# Sheet1.net
KiCad netlist of a schematic drawn in Altium Designer
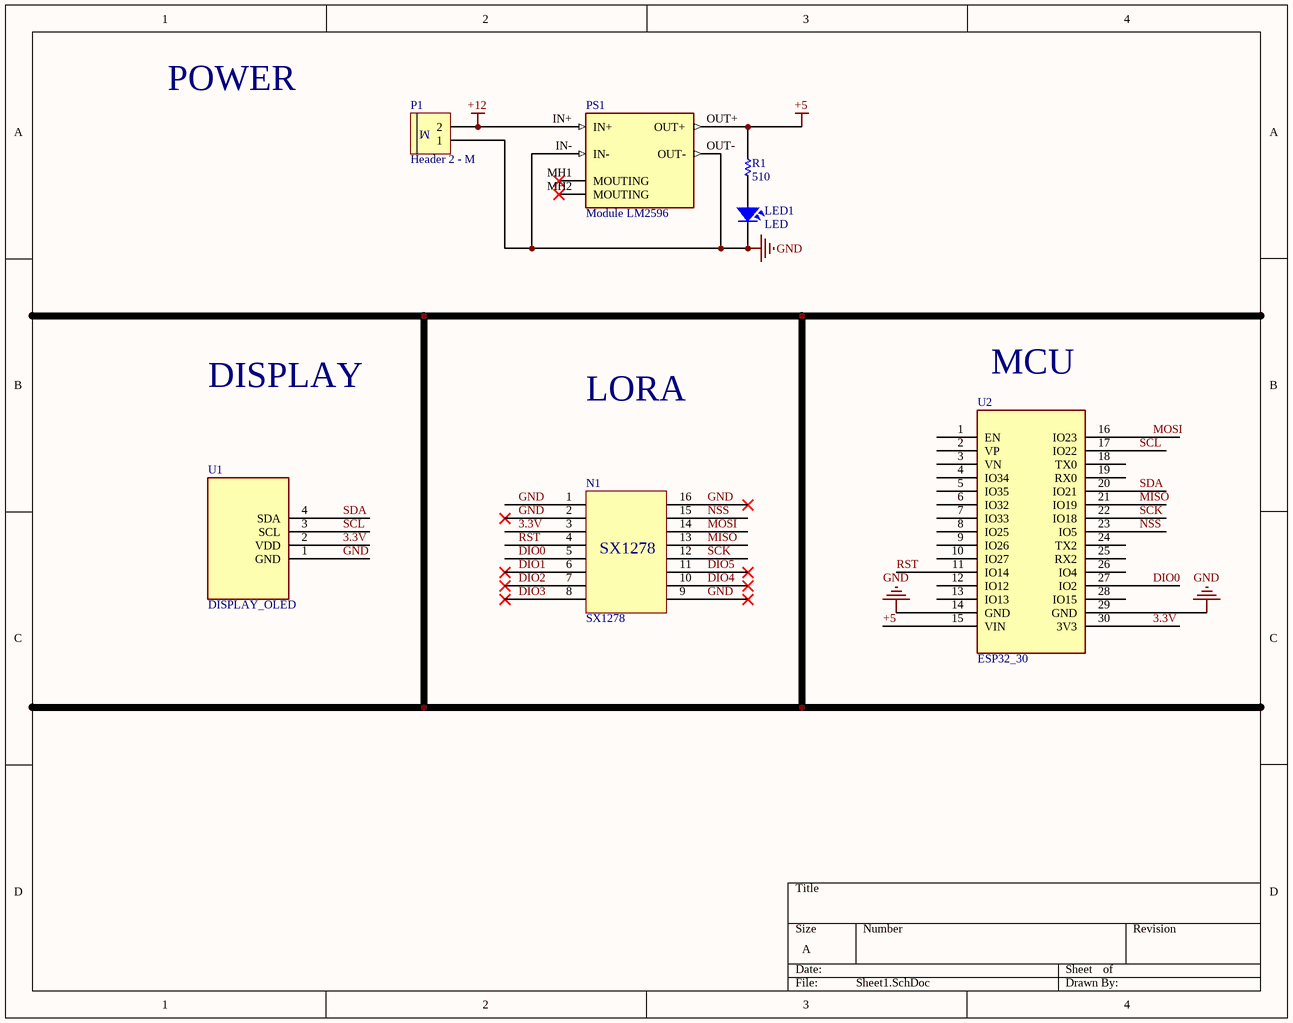
[diagram p0: Sheet1.SchDoc]

(export (version "E")
  (design (tool "Eeschema 10.0.6"))
  (components
    (comp (ref "LED1")
      (value "LED")
      (footprint "LED-3")
      (description "LED Single colour Green and Red")
      (libsource (lib "My Library") (part "LED"))
    )
    (comp (ref "N1") (value "SX1278") (footprint "DIP16") (libsource (lib "TV") (part "SX1278")))
    (comp (ref "P1")
      (value "Header 2 - M")
      (footprint "Medium - Header 2")
      (description "Header, 2-Pin, Medium")
      (fields (field (name "PUBLISHER") "Altium Limited"))
      (libsource (lib "My Library (1)") (part "Header 2 - M"))
    )
    (comp (ref "PS1")
      (value "Module LM2596")
      (footprint "CONV_MC00100")
      (description "DC-DC LM2596 Step Down Adjustable Converter Power Supply Module 1.3V-35V")
      (fields (field (name "MF") "YKS") (field (name "MP") "MC00100"))
      (libsource (lib "LM2596") (part "MC00100"))
    )
    (comp (ref "R1")
      (value "510")
      (footprint "RES-1/2W")
      (description "Res")
      (fields
        (field (name "MANUFACTURER") "Generic Components")
        (field (name "PUBLISHER") "Altium Hobart Technology Centre")
      )
      (libsource (lib "Altium Library") (part "Res"))
    )
    (comp (ref "U1")
      (value "DISPLAY_OLED")
      (footprint "DISPLAY_OLED")
      (description "Display Oled 128x64 0.96\" I2C.")
      (libsource (lib "Displays") (part "DISPLAY_OLED"))
    )
    (comp (ref "U2")
      (value "ESP32_30")
      (footprint "ESP32_30")
      (description "Microcontoller Board 30 Pins Wifi 2.4GHz BLE 4.2 ESP32-WROOM-32D")
      (libsource (lib "Espressif Microcontrollers") (part "ESP32_30"))
    )
  )
  (nets
    (net (code "1") (name "+5") (class "Default")
      (node (ref "PS1") (pin "OUT+") (pinfunction "OUT+_OUT+") (pintype "output"))
      (node (ref "R1") (pin "1") (pinfunction "1_1") (pintype "passive"))
      (node (ref "U2") (pin "15") (pinfunction "VIN_15") (pintype "passive"))
    )
    (net (code "2") (name "+12") (class "Default")
      (node (ref "P1") (pin "2") (pinfunction "2_2") (pintype "passive"))
      (node (ref "PS1") (pin "IN+") (pinfunction "IN+_IN+") (pintype "input"))
    )
    (net (code "3") (name "/3.3V") (class "Default")
      (node (ref "N1") (pin "3") (pinfunction "3_3") (pintype "passive"))
      (node (ref "U1") (pin "2") (pinfunction "VDD_2") (pintype "tri_state"))
      (node (ref "U2") (pin "30") (pinfunction "3V3_30") (pintype "passive"))
    )
    (net (code "4") (name "/DIO0") (class "Default")
      (node (ref "N1") (pin "5") (pinfunction "5_5") (pintype "passive"))
      (node (ref "U2") (pin "27") (pinfunction "IO2_27") (pintype "passive"))
    )
    (net (code "5") (name "/DIO1") (class "Default")
      (node (ref "N1") (pin "6") (pinfunction "6_6") (pintype "passive+no_connect"))
    )
    (net (code "6") (name "/DIO2") (class "Default")
      (node (ref "N1") (pin "7") (pinfunction "7_7") (pintype "passive+no_connect"))
    )
    (net (code "7") (name "/DIO3") (class "Default")
      (node (ref "N1") (pin "8") (pinfunction "8_8") (pintype "passive+no_connect"))
    )
    (net (code "8") (name "/DIO4") (class "Default")
      (node (ref "N1") (pin "10") (pinfunction "10_10") (pintype "passive+no_connect"))
    )
    (net (code "9") (name "/DIO5") (class "Default")
      (node (ref "N1") (pin "11") (pinfunction "11_11") (pintype "passive+no_connect"))
    )
    (net (code "10") (name "/MISO") (class "Default")
      (node (ref "N1") (pin "13") (pinfunction "13_13") (pintype "passive"))
      (node (ref "U2") (pin "21") (pinfunction "IO19_21") (pintype "passive"))
    )
    (net (code "11") (name "/MOSI") (class "Default")
      (node (ref "N1") (pin "14") (pinfunction "14_14") (pintype "passive"))
      (node (ref "U2") (pin "16") (pinfunction "IO23_16") (pintype "passive"))
    )
    (net (code "12") (name "/NSS") (class "Default")
      (node (ref "N1") (pin "15") (pinfunction "15_15") (pintype "passive"))
      (node (ref "U2") (pin "23") (pinfunction "IO5_23") (pintype "passive"))
    )
    (net (code "13") (name "/RST") (class "Default")
      (node (ref "N1") (pin "4") (pinfunction "4_4") (pintype "passive"))
      (node (ref "U2") (pin "11") (pinfunction "IO14_11") (pintype "passive"))
    )
    (net (code "14") (name "/SCK") (class "Default")
      (node (ref "N1") (pin "12") (pinfunction "12_12") (pintype "passive"))
      (node (ref "U2") (pin "22") (pinfunction "IO18_22") (pintype "passive"))
    )
    (net (code "15") (name "/SCL") (class "Default")
      (node (ref "U1") (pin "3") (pinfunction "SCL_3") (pintype "tri_state"))
      (node (ref "U2") (pin "17") (pinfunction "IO22_17") (pintype "passive"))
    )
    (net (code "16") (name "/SDA") (class "Default")
      (node (ref "U1") (pin "4") (pinfunction "SDA_4") (pintype "tri_state"))
      (node (ref "U2") (pin "20") (pinfunction "IO21_20") (pintype "passive"))
    )
    (net (code "17") (name "GND") (class "Default")
      (node (ref "LED1") (pin "2") (pinfunction "2_2") (pintype "passive"))
      (node (ref "N1") (pin "1") (pinfunction "1_1") (pintype "passive"))
      (node (ref "N1") (pin "16") (pinfunction "16_16") (pintype "passive"))
      (node (ref "N1") (pin "2") (pinfunction "2_2") (pintype "passive"))
      (node (ref "N1") (pin "9") (pinfunction "9_9") (pintype "passive"))
      (node (ref "P1") (pin "1") (pinfunction "1_1") (pintype "passive"))
      (node (ref "PS1") (pin "IN-") (pinfunction "IN-_IN-") (pintype "input"))
      (node (ref "PS1") (pin "OUT-") (pinfunction "OUT-_OUT-") (pintype "output"))
      (node (ref "U1") (pin "1") (pinfunction "GND_1") (pintype "tri_state"))
      (node (ref "U2") (pin "14") (pinfunction "GND_14") (pintype "passive"))
      (node (ref "U2") (pin "29") (pinfunction "GND_29") (pintype "passive"))
    )
    (net (code "18") (name "Net-(LED1-Pad1)") (class "Default")
      (node (ref "LED1") (pin "1") (pinfunction "1_1") (pintype "passive"))
      (node (ref "R1") (pin "2") (pinfunction "2_2") (pintype "passive"))
    )
    (net (code "19") (name "unconnected-(PS1-MOUTING-PadMH1)") (class "Default")
      (node (ref "PS1") (pin "MH1") (pinfunction "MOUTING_MH1") (pintype "passive+no_connect"))
    )
    (net (code "20") (name "unconnected-(PS1-MOUTING-PadMH2)") (class "Default")
      (node (ref "PS1") (pin "MH2") (pinfunction "MOUTING_MH2") (pintype "passive+no_connect"))
    )
    (net (code "21") (name "unconnected-(U2-EN-Pad1)") (class "Default")
      (node (ref "U2") (pin "1") (pinfunction "EN_1") (pintype "passive"))
    )
    (net (code "22") (name "unconnected-(U2-IO4-Pad26)") (class "Default")
      (node (ref "U2") (pin "26") (pinfunction "IO4_26") (pintype "passive"))
    )
    (net (code "23") (name "unconnected-(U2-IO12-Pad12)") (class "Default")
      (node (ref "U2") (pin "12") (pinfunction "IO12_12") (pintype "passive"))
    )
    (net (code "24") (name "unconnected-(U2-IO13-Pad13)") (class "Default")
      (node (ref "U2") (pin "13") (pinfunction "IO13_13") (pintype "passive"))
    )
    (net (code "25") (name "unconnected-(U2-IO15-Pad28)") (class "Default")
      (node (ref "U2") (pin "28") (pinfunction "IO15_28") (pintype "passive"))
    )
    (net (code "26") (name "unconnected-(U2-IO25-Pad8)") (class "Default")
      (node (ref "U2") (pin "8") (pinfunction "IO25_8") (pintype "passive"))
    )
    (net (code "27") (name "unconnected-(U2-IO26-Pad9)") (class "Default")
      (node (ref "U2") (pin "9") (pinfunction "IO26_9") (pintype "passive"))
    )
    (net (code "28") (name "unconnected-(U2-IO27-Pad10)") (class "Default")
      (node (ref "U2") (pin "10") (pinfunction "IO27_10") (pintype "passive"))
    )
    (net (code "29") (name "unconnected-(U2-IO32-Pad6)") (class "Default")
      (node (ref "U2") (pin "6") (pinfunction "IO32_6") (pintype "passive"))
    )
    (net (code "30") (name "unconnected-(U2-IO33-Pad7)") (class "Default")
      (node (ref "U2") (pin "7") (pinfunction "IO33_7") (pintype "passive"))
    )
    (net (code "31") (name "unconnected-(U2-IO34-Pad4)") (class "Default")
      (node (ref "U2") (pin "4") (pinfunction "IO34_4") (pintype "passive"))
    )
    (net (code "32") (name "unconnected-(U2-IO35-Pad5)") (class "Default")
      (node (ref "U2") (pin "5") (pinfunction "IO35_5") (pintype "passive"))
    )
    (net (code "33") (name "unconnected-(U2-RX0-Pad19)") (class "Default")
      (node (ref "U2") (pin "19") (pinfunction "RX0_19") (pintype "passive"))
    )
    (net (code "34") (name "unconnected-(U2-RX2-Pad25)") (class "Default")
      (node (ref "U2") (pin "25") (pinfunction "RX2_25") (pintype "passive"))
    )
    (net (code "35") (name "unconnected-(U2-TX0-Pad18)") (class "Default")
      (node (ref "U2") (pin "18") (pinfunction "TX0_18") (pintype "passive"))
    )
    (net (code "36") (name "unconnected-(U2-TX2-Pad24)") (class "Default")
      (node (ref "U2") (pin "24") (pinfunction "TX2_24") (pintype "passive"))
    )
    (net (code "37") (name "unconnected-(U2-VN-Pad3)") (class "Default")
      (node (ref "U2") (pin "3") (pinfunction "VN_3") (pintype "passive"))
    )
    (net (code "38") (name "unconnected-(U2-VP-Pad2)") (class "Default")
      (node (ref "U2") (pin "2") (pinfunction "VP_2") (pintype "passive"))
    )
  )
)
